# artik530_carrierboard.net
KiCad netlist of a schematic drawn in EAGLE
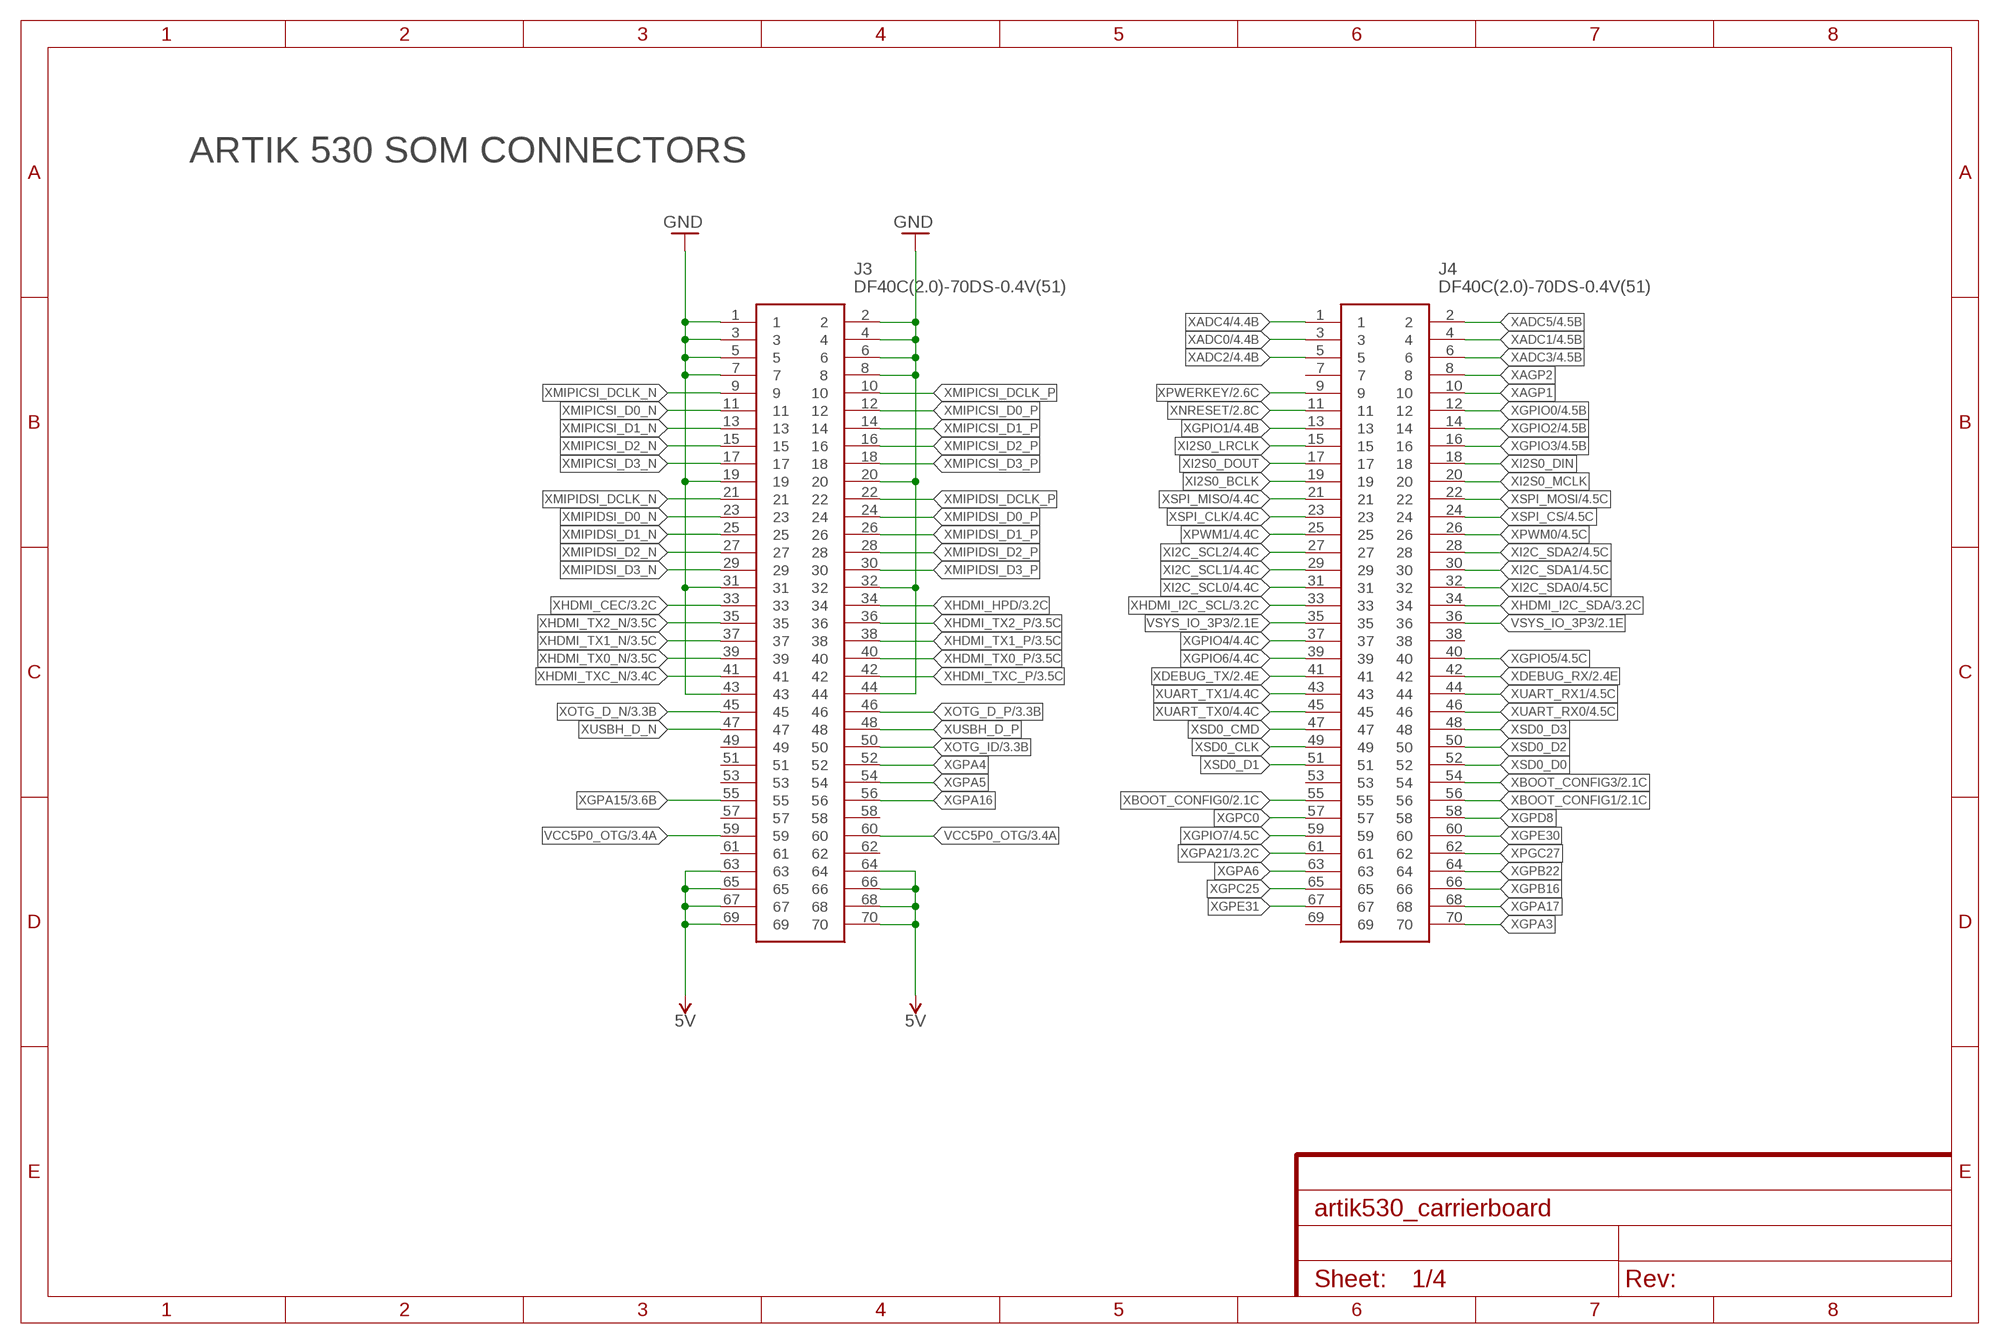
[diagram p0: schematic, sheet 1]
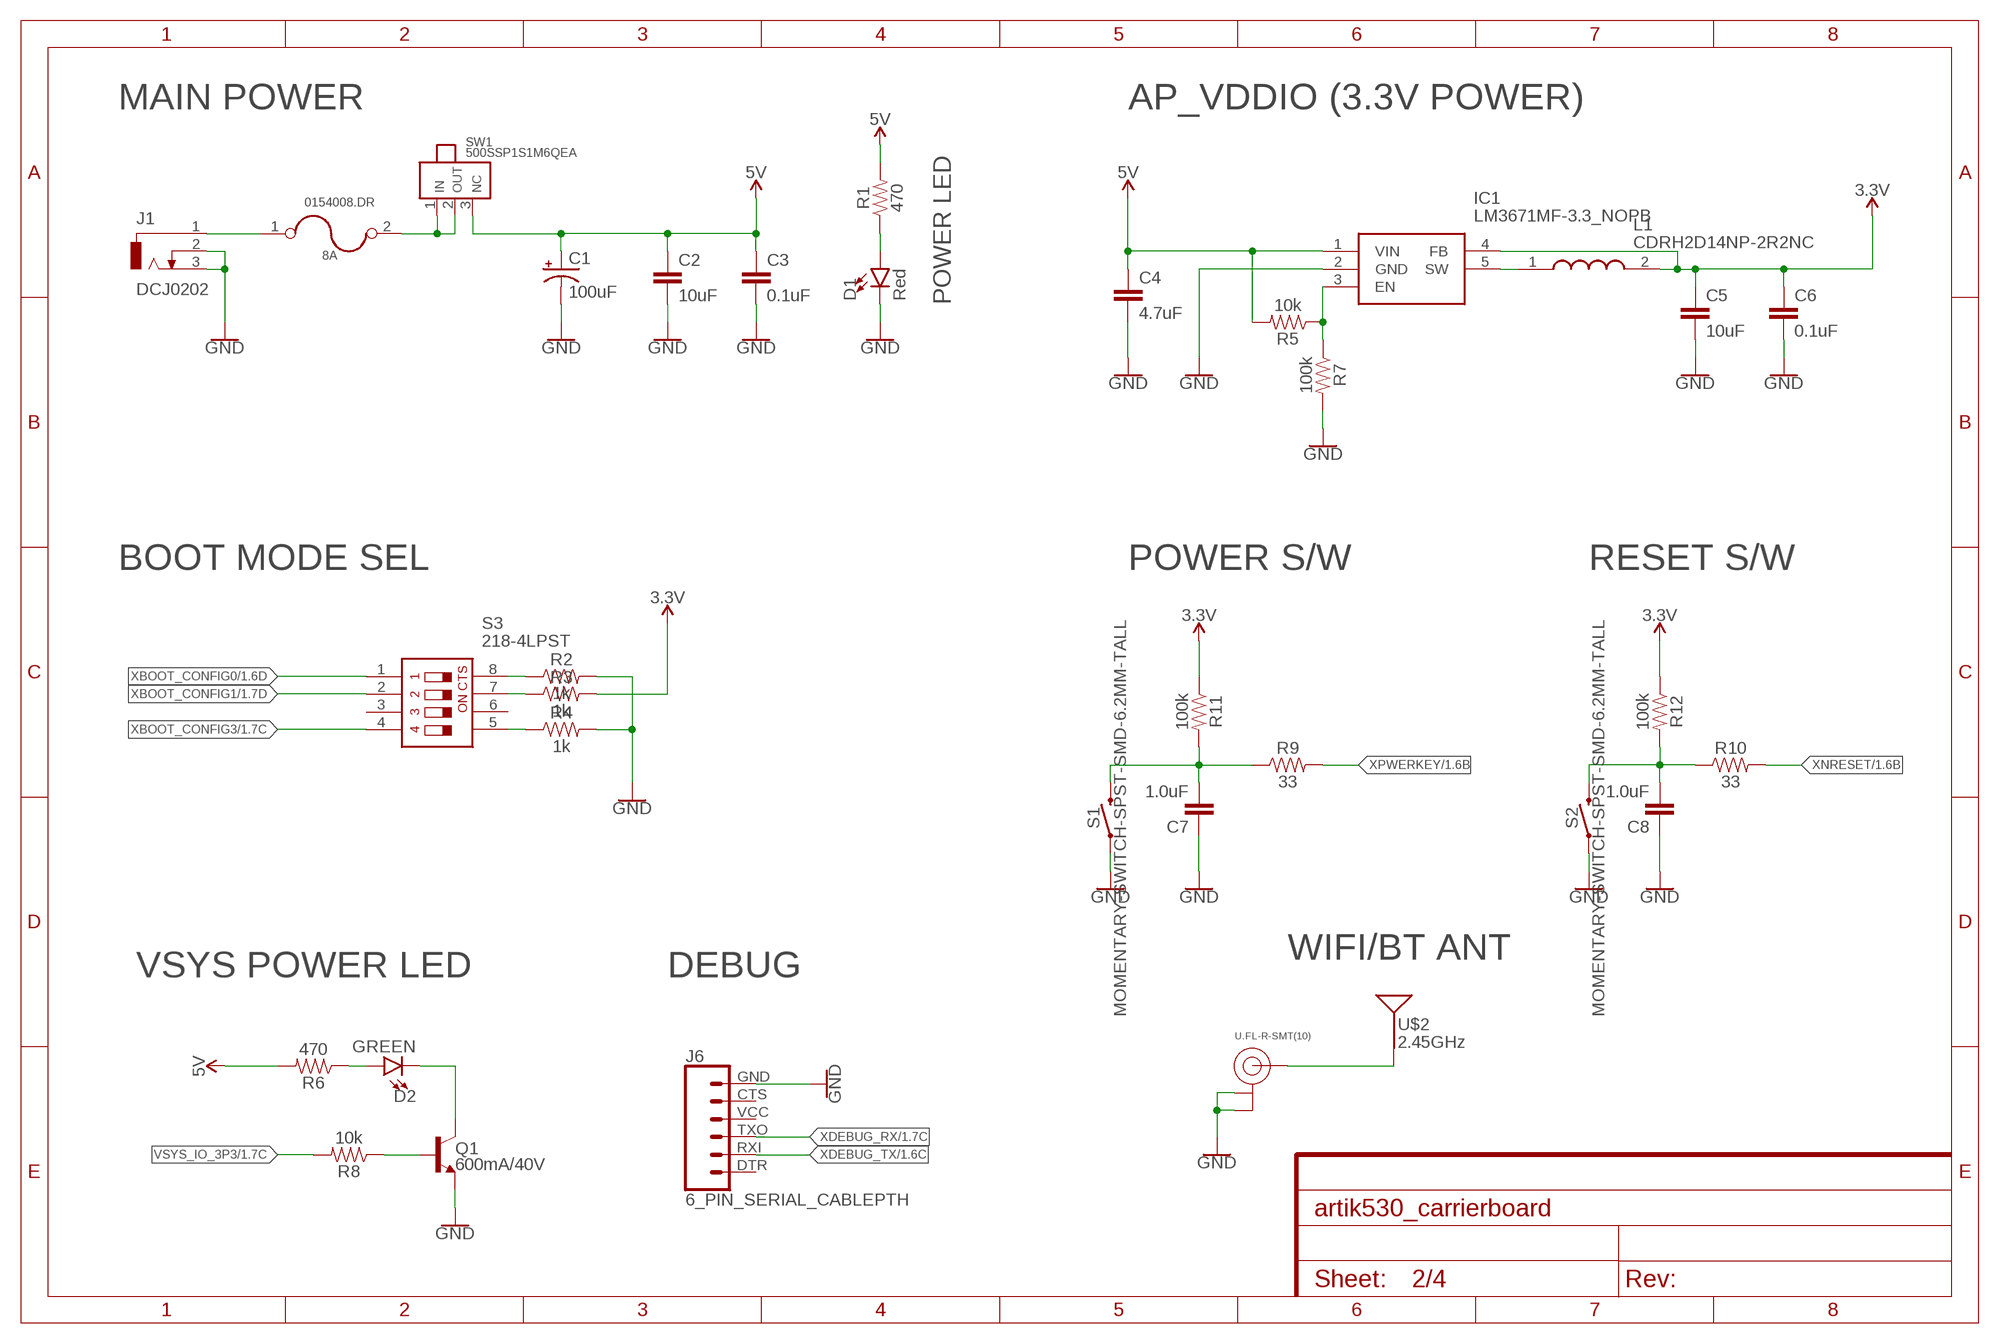
[diagram p1: schematic, sheet 2]
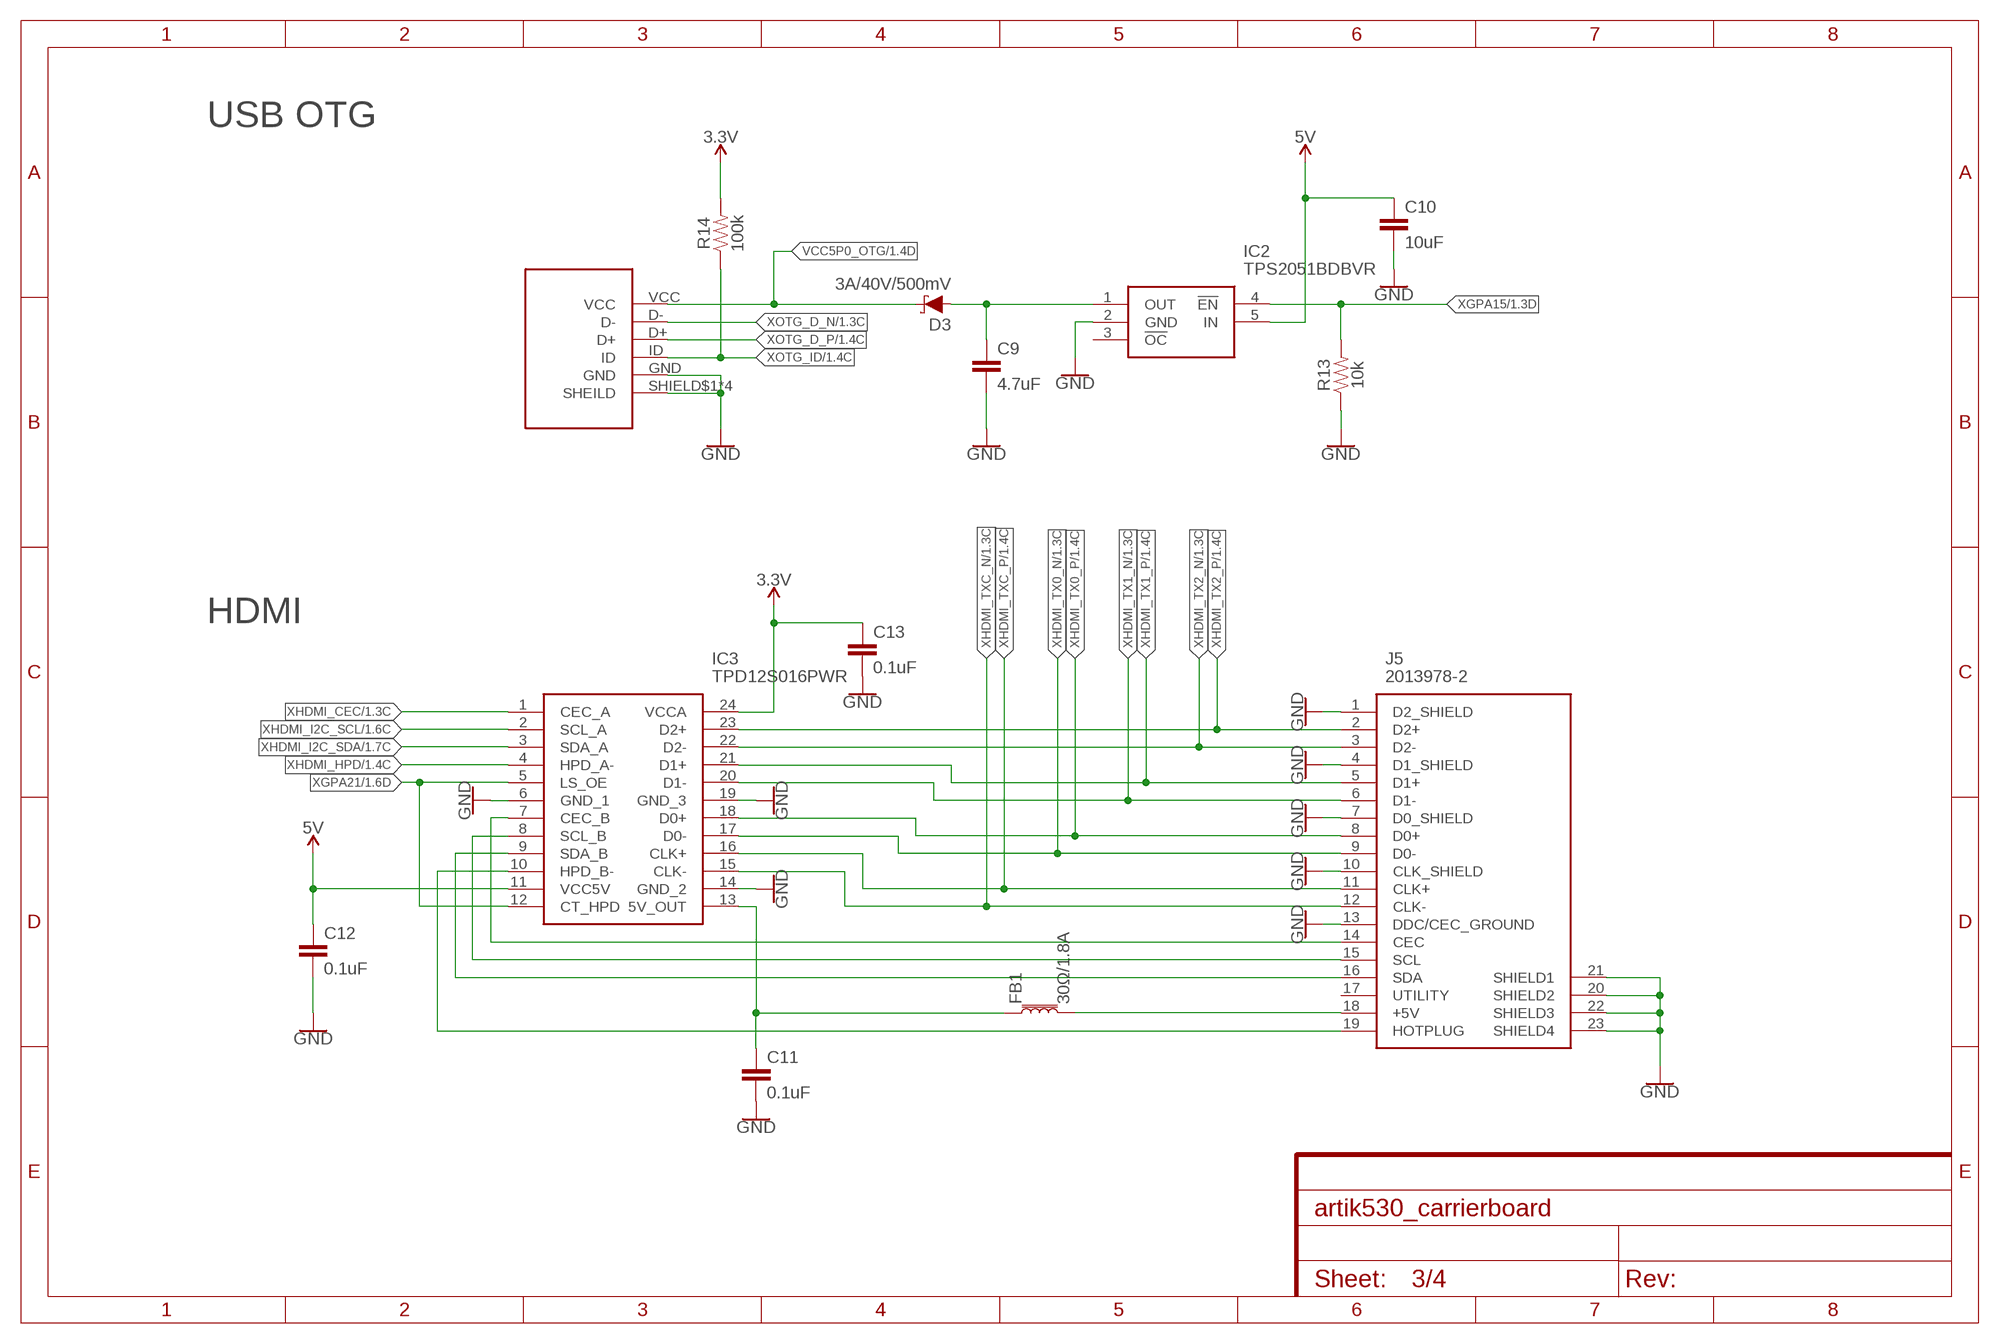
[diagram p2: schematic, sheet 3]
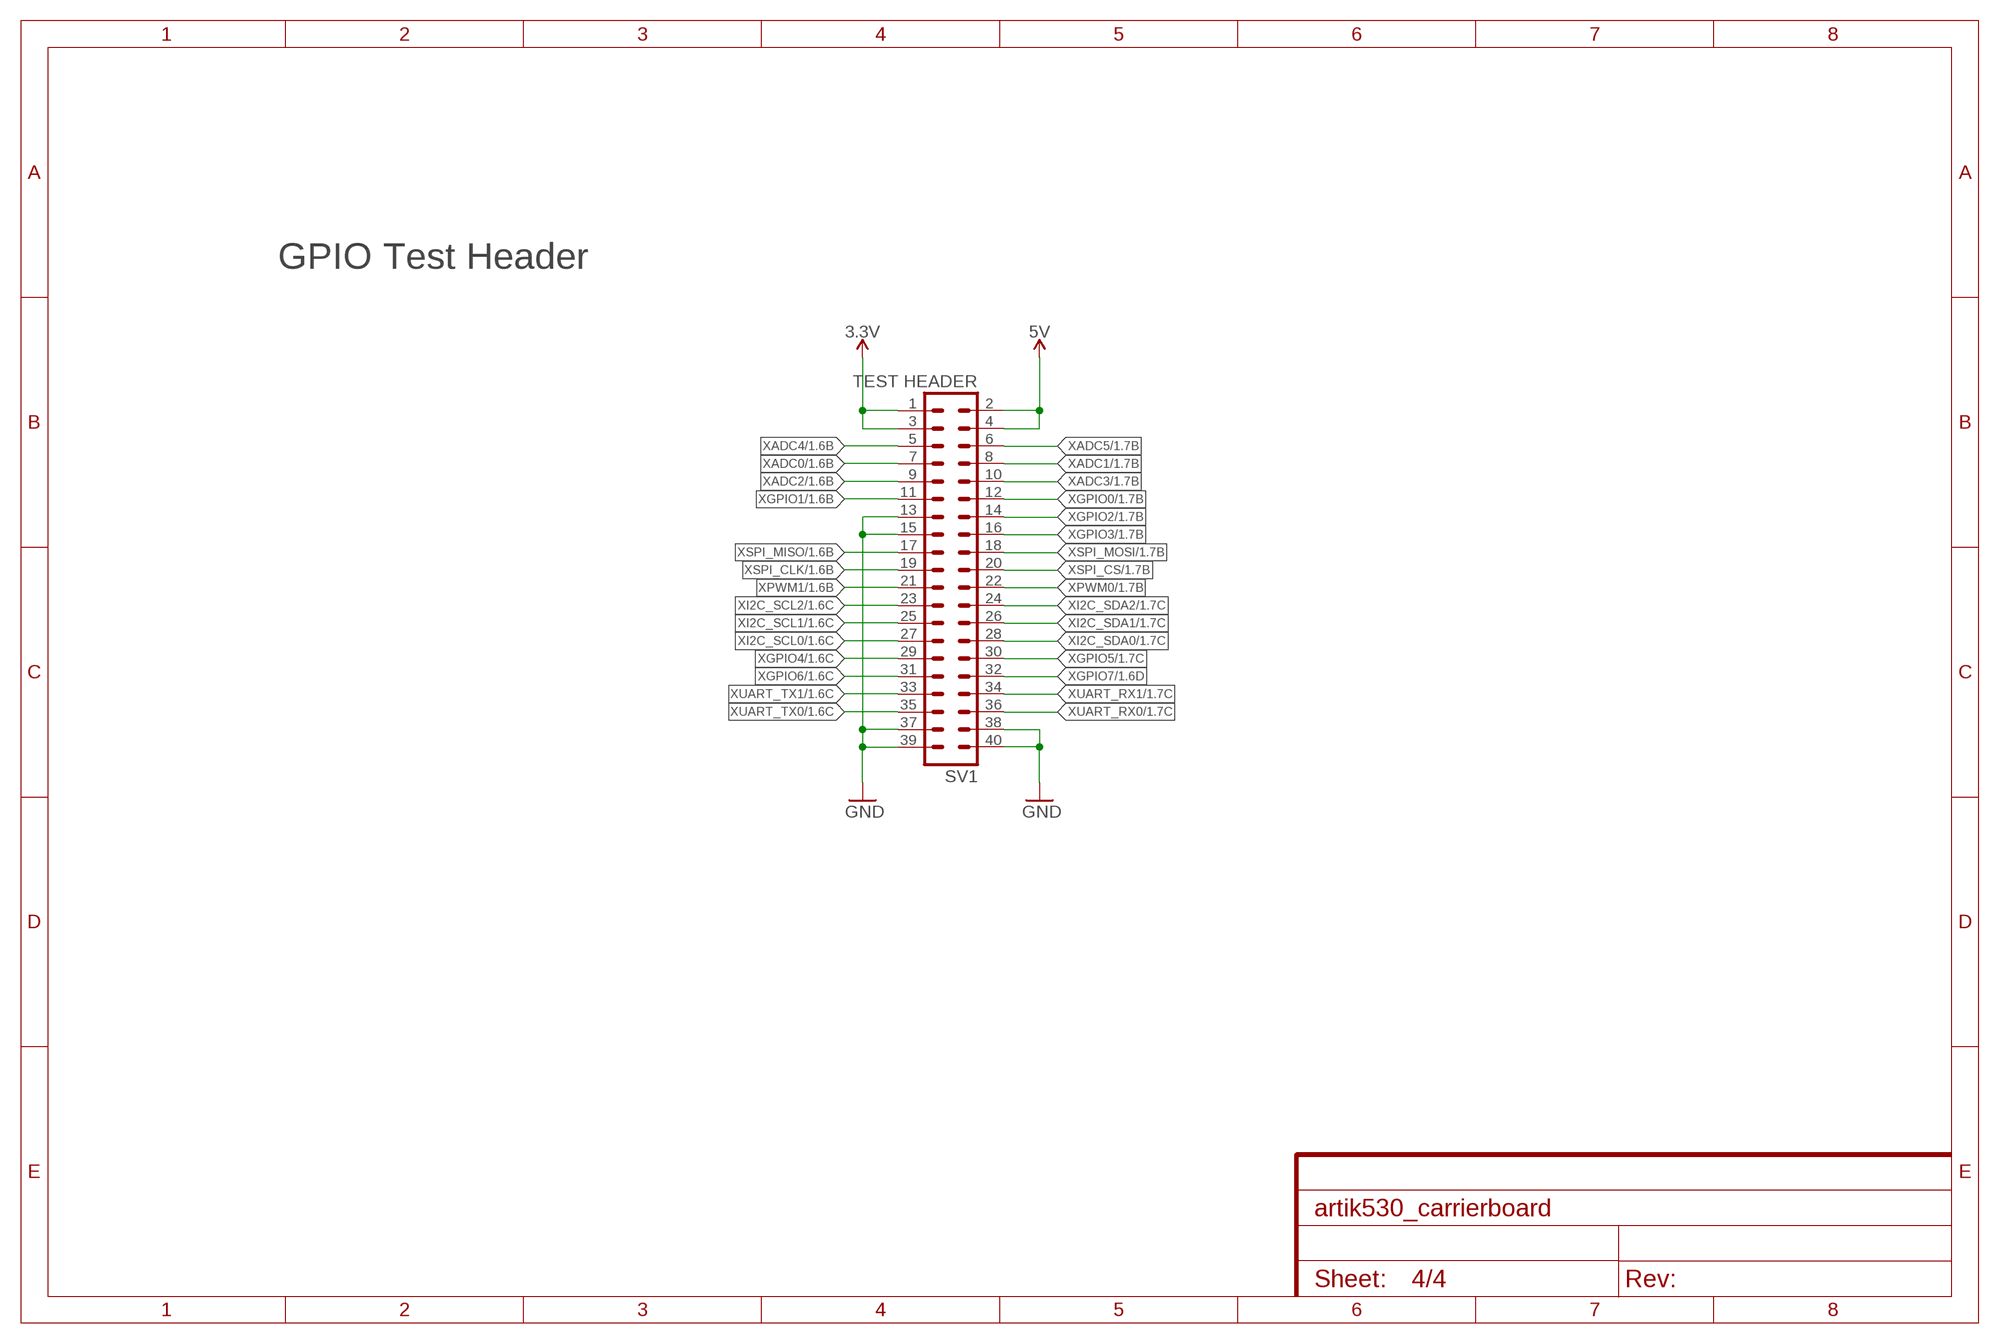
[diagram p3: schematic, sheet 4]

(export (version "E")
  (design (tool "Eeschema 10.0.6"))
  (components
    (comp (ref "J3")
      (value "DF40C(2.0)-70DS-0.4V(51)")
      (footprint "eagle-import:DF40C(2.0)-70DS-0.4V(51)")
      (libsource (lib "eagle-import") (part "DF40C(2.0)-70DS-0.4V(51)"))
    )
    (comp (ref "J4")
      (value "DF40C(2.0)-70DS-0.4V(51)")
      (footprint "eagle-import:DF40C(2.0)-70DS-0.4V(51)")
      (libsource (lib "eagle-import") (part "DF40C(2.0)-70DS-0.4V(51)"))
    )
    (comp (ref "SV1")
      (value "TEST HEADER")
      (footprint "eagle-import:MA20-2")
      (libsource (lib "eagle-import") (part "MA20-2"))
    )
    (comp (ref "C9")
      (value "4.7uF")
      (footprint "eagle-import:0603")
      (libsource (lib "eagle-import") (part "4.7UF-0603-6.3V-(10%)"))
    )
    (comp (ref "C10")
      (value "10uF")
      (footprint "eagle-import:0603")
      (libsource (lib "eagle-import") (part "10UF-0603-6.3V-20%"))
    )
    (comp (ref "C11")
      (value "0.1uF")
      (footprint "eagle-import:0603")
      (libsource (lib "eagle-import") (part "0.1UF-0603-25V-(+80/-20%)"))
    )
    (comp (ref "C12")
      (value "0.1uF")
      (footprint "eagle-import:0603")
      (libsource (lib "eagle-import") (part "0.1UF-0603-25V-(+80/-20%)"))
    )
    (comp (ref "C13")
      (value "0.1uF")
      (footprint "eagle-import:0603")
      (libsource (lib "eagle-import") (part "0.1UF-0603-25V-(+80/-20%)"))
    )
    (comp (ref "D3")
      (value "3A/40V/500mV")
      (footprint "eagle-import:SMA-DIODE")
      (libsource (lib "eagle-import") (part "DIODE-SCHOTTKY-B340A"))
    )
    (comp (ref "FB1")
      (value "30Ω/1.8A")
      (footprint "eagle-import:0603")
      (libsource (lib "eagle-import") (part "FERRITE_BEAD-0603"))
    )
    (comp (ref "IC2")
      (value "TPS2051BDBVR")
      (footprint "eagle-import:SOT95P280X145-5N")
      (libsource (lib "eagle-import") (part "TPS2051BDBVR"))
    )
    (comp (ref "IC3")
      (value "TPD12S016PWR")
      (footprint "eagle-import:SOP65P640X120-24N")
      (fields (field (name "RS_PART_NUMBER") "1627865"))
      (libsource (lib "eagle-import") (part "TPD12S016PWR"))
    )
    (comp (ref "J2")
      (value "10118193-0001LF")
      (footprint "eagle-import:10118193-0001LF")
      (libsource (lib "eagle-import") (part "10118193-0001LF"))
    )
    (comp (ref "J5")
      (value "2013978-2")
      (footprint "eagle-import:20139782")
      (libsource (lib "eagle-import") (part "2013978-2"))
    )
    (comp (ref "R13")
      (value "10k")
      (footprint "eagle-import:0603")
      (libsource (lib "eagle-import") (part "10KOHM-0603-1/10W-1%"))
    )
    (comp (ref "R14")
      (value "100k")
      (footprint "eagle-import:0603")
      (libsource (lib "eagle-import") (part "100KOHM-0603-1/10W-1%"))
    )
    (comp (ref "C1")
      (value "100uF")
      (footprint "eagle-import:EIA7343")
      (libsource (lib "eagle-import") (part "100UF-POLAR-EIA7343-10V-10%(TANT)"))
    )
    (comp (ref "C2")
      (value "10uF")
      (footprint "eagle-import:0603")
      (libsource (lib "eagle-import") (part "10UF-0603-6.3V-20%"))
    )
    (comp (ref "C3")
      (value "0.1uF")
      (footprint "eagle-import:0603")
      (libsource (lib "eagle-import") (part "0.1UF-0603-25V-(+80/-20%)"))
    )
    (comp (ref "C4")
      (value "4.7uF")
      (footprint "eagle-import:0603")
      (libsource (lib "eagle-import") (part "4.7UF-0603-6.3V-(10%)"))
    )
    (comp (ref "C5")
      (value "10uF")
      (footprint "eagle-import:0603")
      (libsource (lib "eagle-import") (part "10UF-0603-6.3V-20%"))
    )
    (comp (ref "C6")
      (value "0.1uF")
      (footprint "eagle-import:0603")
      (libsource (lib "eagle-import") (part "0.1UF-0603-25V-(+80/-20%)"))
    )
    (comp (ref "C7")
      (value "1.0uF")
      (footprint "eagle-import:0603")
      (libsource (lib "eagle-import") (part "1.0UF-0603-16V-10%"))
    )
    (comp (ref "C8")
      (value "1.0uF")
      (footprint "eagle-import:0603")
      (libsource (lib "eagle-import") (part "1.0UF-0603-16V-10%"))
    )
    (comp (ref "D1")
      (value "Red")
      (footprint "eagle-import:LED-0603")
      (libsource (lib "eagle-import") (part "LED-RED0603-SMART"))
    )
    (comp (ref "D2")
      (value "GREEN")
      (footprint "eagle-import:LED-0603")
      (libsource (lib "eagle-import") (part "LED-GREEN0603"))
    )
    (comp (ref "IC1")
      (value "LM3671MF-3.3_NOPB")
      (footprint "eagle-import:SOT95P284X122-5N")
      (fields
        (field (name "DIGIKEY_PART_NUMBER") "LM3671MF-3.3/NOPBTR-ND")
        (field (name "MANUFACTURER_PART_NUMBER") "LM3671MF-3.3/NOPB")
      )
      (libsource (lib "eagle-import") (part "LM3671MF-3.3_NOPB"))
    )
    (comp (ref "J1")
      (value "DCJ0202")
      (footprint "eagle-import:DCJ0202")
      (libsource (lib "eagle-import") (part "DCJ0202"))
    )
    (comp (ref "J6")
      (value "6_PIN_SERIAL_CABLEPTH")
      (footprint "eagle-import:FTDI_BASIC")
      (libsource (lib "eagle-import") (part "6_PIN_SERIAL_CABLEPTH"))
    )
    (comp (ref "L1")
      (value "CDRH2D14NP-2R2NC")
      (footprint "eagle-import:CDRH2D14")
      (libsource (lib "eagle-import") (part "CDRH2D14NP-2R2NC"))
    )
    (comp (ref "Q1")
      (value "600mA/40V")
      (footprint "eagle-import:SOT23-3")
      (libsource (lib "eagle-import") (part "TRANS_NPN-MMBT2222AL"))
    )
    (comp (ref "R1")
      (value "470")
      (footprint "eagle-import:0603")
      (libsource (lib "eagle-import") (part "470OHM-0603-1/10W-1%"))
    )
    (comp (ref "R2")
      (value "1k")
      (footprint "eagle-import:0603")
      (libsource (lib "eagle-import") (part "1KOHM-0603-1/10W-1%"))
    )
    (comp (ref "R3")
      (value "1k")
      (footprint "eagle-import:0603")
      (libsource (lib "eagle-import") (part "1KOHM-0603-1/10W-1%"))
    )
    (comp (ref "R4")
      (value "1k")
      (footprint "eagle-import:0603")
      (libsource (lib "eagle-import") (part "1KOHM-0603-1/10W-1%"))
    )
    (comp (ref "R5")
      (value "10k")
      (footprint "eagle-import:0603")
      (libsource (lib "eagle-import") (part "10KOHM-0603-1/10W-1%"))
    )
    (comp (ref "R6")
      (value "470")
      (footprint "eagle-import:0603")
      (libsource (lib "eagle-import") (part "470OHM-0603-1/10W-1%"))
    )
    (comp (ref "R7")
      (value "100k")
      (footprint "eagle-import:0603")
      (libsource (lib "eagle-import") (part "100KOHM-0603-1/10W-1%"))
    )
    (comp (ref "R8")
      (value "10k")
      (footprint "eagle-import:0603")
      (libsource (lib "eagle-import") (part "10KOHM-0603-1/10W-1%"))
    )
    (comp (ref "R9")
      (value "33")
      (footprint "eagle-import:0603")
      (libsource (lib "eagle-import") (part "33OHM-0603-1/10W-1%"))
    )
    (comp (ref "R10")
      (value "33")
      (footprint "eagle-import:0603")
      (libsource (lib "eagle-import") (part "33OHM-0603-1/10W-1%"))
    )
    (comp (ref "R11")
      (value "100k")
      (footprint "eagle-import:0603")
      (libsource (lib "eagle-import") (part "100KOHM-0603-1/10W-1%"))
    )
    (comp (ref "R12")
      (value "100k")
      (footprint "eagle-import:0603")
      (libsource (lib "eagle-import") (part "100KOHM-0603-1/10W-1%"))
    )
    (comp (ref "S1")
      (value "MOMENTARY-SWITCH-SPST-SMD-6.2MM-TALL")
      (footprint "eagle-import:TACTILE_SWITCH_SMD_6.2MM_TALL")
      (libsource (lib "eagle-import") (part "MOMENTARY-SWITCH-SPST-SMD-6.2MM-TALL"))
    )
    (comp (ref "S2")
      (value "MOMENTARY-SWITCH-SPST-SMD-6.2MM-TALL")
      (footprint "eagle-import:TACTILE_SWITCH_SMD_6.2MM_TALL")
      (libsource (lib "eagle-import") (part "MOMENTARY-SWITCH-SPST-SMD-6.2MM-TALL"))
    )
    (comp (ref "S3")
      (value "218-4LPST")
      (footprint "eagle-import:SOIC127P844X265-8N")
      (libsource (lib "eagle-import") (part "218-4LPST"))
    )
    (comp (ref "SW1")
      (value "500SSP1S1M6QEA")
      (footprint "eagle-import:500SSP1S1M6QEA")
      (libsource (lib "eagle-import") (part "500SSP1S1M6QEA"))
    )
    (comp (ref "U$1")
      (value "0154008.DR")
      (footprint "eagle-import:0154008.DR")
      (libsource (lib "eagle-import") (part "0154008.DR"))
    )
    (comp (ref "U$2")
      (value "2.45GHz")
      (footprint "eagle-import:ANT-2.4GHZ-6.5X2.2MM")
      (libsource (lib "eagle-import") (part "ANTENNA2.4GHZ-6.5X2.2MM"))
    )
    (comp (ref "U$3")
      (value "U.FL-R-SMT(10)")
      (footprint "eagle-import:U.FL-R-SMT(10)")
      (libsource (lib "eagle-import") (part "U.FL-R-SMT(10)"))
    )
  )
  (nets
    (net (code "1") (name "3.3V") (class "Default")
      (node (ref "C13") (pin "1") (pinfunction "1_1") (pintype "passive"))
      (node (ref "C5") (pin "1") (pinfunction "1_1") (pintype "passive"))
      (node (ref "C6") (pin "1") (pinfunction "1_1") (pintype "passive"))
      (node (ref "IC1") (pin "4") (pinfunction "FB_4") (pintype "bidirectional"))
      (node (ref "IC3") (pin "24") (pinfunction "VCCA_24") (pintype "bidirectional"))
      (node (ref "L1") (pin "2") (pinfunction "2_2") (pintype "bidirectional"))
      (node (ref "R11") (pin "1") (pinfunction "1_1") (pintype "passive"))
      (node (ref "R12") (pin "1") (pinfunction "1_1") (pintype "passive"))
      (node (ref "R14") (pin "2") (pinfunction "2_2") (pintype "passive"))
      (node (ref "R3") (pin "2") (pinfunction "2_2") (pintype "passive"))
      (node (ref "SV1") (pin "1") (pinfunction "1_1") (pintype "passive"))
      (node (ref "SV1") (pin "3") (pinfunction "3_3") (pintype "passive"))
    )
    (net (code "2") (name "5V") (class "Default")
      (node (ref "C1") (pin "A") (pinfunction "+_A") (pintype "passive"))
      (node (ref "C10") (pin "1") (pinfunction "1_1") (pintype "passive"))
      (node (ref "C12") (pin "1") (pinfunction "1_1") (pintype "passive"))
      (node (ref "C2") (pin "1") (pinfunction "1_1") (pintype "passive"))
      (node (ref "C3") (pin "1") (pinfunction "1_1") (pintype "passive"))
      (node (ref "C4") (pin "1") (pinfunction "1_1") (pintype "passive"))
      (node (ref "IC1") (pin "1") (pinfunction "VIN_1") (pintype "bidirectional"))
      (node (ref "IC2") (pin "5") (pinfunction "IN_5") (pintype "input"))
      (node (ref "IC3") (pin "11") (pinfunction "VCC5V_11") (pintype "bidirectional"))
      (node (ref "J3") (pin "63") (pinfunction "63_63") (pintype "bidirectional"))
      (node (ref "J3") (pin "64") (pinfunction "64_64") (pintype "bidirectional"))
      (node (ref "J3") (pin "65") (pinfunction "65_65") (pintype "bidirectional"))
      (node (ref "J3") (pin "66") (pinfunction "66_66") (pintype "bidirectional"))
      (node (ref "J3") (pin "67") (pinfunction "67_67") (pintype "bidirectional"))
      (node (ref "J3") (pin "68") (pinfunction "68_68") (pintype "bidirectional"))
      (node (ref "J3") (pin "69") (pinfunction "69_69") (pintype "bidirectional"))
      (node (ref "J3") (pin "70") (pinfunction "70_70") (pintype "bidirectional"))
      (node (ref "R1") (pin "2") (pinfunction "2_2") (pintype "passive"))
      (node (ref "R5") (pin "2") (pinfunction "2_2") (pintype "passive"))
      (node (ref "R6") (pin "2") (pinfunction "2_2") (pintype "passive"))
      (node (ref "SV1") (pin "2") (pinfunction "2_2") (pintype "passive"))
      (node (ref "SV1") (pin "4") (pinfunction "4_4") (pintype "passive"))
      (node (ref "SW1") (pin "3") (pinfunction "NC_3") (pintype "bidirectional"))
    )
    (net (code "3") (name "GND") (class "Default")
      (node (ref "C1") (pin "C") (pinfunction "-_C") (pintype "passive"))
      (node (ref "C10") (pin "2") (pinfunction "2_2") (pintype "passive"))
      (node (ref "C11") (pin "2") (pinfunction "2_2") (pintype "passive"))
      (node (ref "C12") (pin "2") (pinfunction "2_2") (pintype "passive"))
      (node (ref "C13") (pin "2") (pinfunction "2_2") (pintype "passive"))
      (node (ref "C2") (pin "2") (pinfunction "2_2") (pintype "passive"))
      (node (ref "C3") (pin "2") (pinfunction "2_2") (pintype "passive"))
      (node (ref "C4") (pin "2") (pinfunction "2_2") (pintype "passive"))
      (node (ref "C5") (pin "2") (pinfunction "2_2") (pintype "passive"))
      (node (ref "C6") (pin "2") (pinfunction "2_2") (pintype "passive"))
      (node (ref "C7") (pin "1") (pinfunction "1_1") (pintype "passive"))
      (node (ref "C8") (pin "1") (pinfunction "1_1") (pintype "passive"))
      (node (ref "C9") (pin "2") (pinfunction "2_2") (pintype "passive"))
      (node (ref "D1") (pin "C") (pinfunction "C_C") (pintype "passive"))
      (node (ref "IC1") (pin "2") (pinfunction "GND_2") (pintype "bidirectional"))
      (node (ref "IC2") (pin "2") (pinfunction "GND_2") (pintype "power_in"))
      (node (ref "IC3") (pin "14") (pinfunction "GND_2_14") (pintype "bidirectional"))
      (node (ref "IC3") (pin "19") (pinfunction "GND_3_19") (pintype "bidirectional"))
      (node (ref "IC3") (pin "6") (pinfunction "GND_1_6") (pintype "bidirectional"))
      (node (ref "J1") (pin "2") (pinfunction "2_2") (pintype "passive"))
      (node (ref "J1") (pin "3") (pinfunction "3_3") (pintype "passive"))
      (node (ref "J2") (pin "GND") (pinfunction "GND_GND") (pintype "bidirectional"))
      (node (ref "J2") (pin "SHIELD$1") (pinfunction "SHEILD_SHIELD$1") (pintype "bidirectional"))
      (node (ref "J2") (pin "SHIELD$2") (pinfunction "SHEILD_SHIELD$2") (pintype "bidirectional"))
      (node (ref "J2") (pin "SHIELD$3") (pinfunction "SHEILD_SHIELD$3") (pintype "bidirectional"))
      (node (ref "J2") (pin "SHIELD$4") (pinfunction "SHEILD_SHIELD$4") (pintype "bidirectional"))
      (node (ref "J3") (pin "1") (pinfunction "1_1") (pintype "bidirectional"))
      (node (ref "J3") (pin "19") (pinfunction "19_19") (pintype "bidirectional"))
      (node (ref "J3") (pin "2") (pinfunction "2_2") (pintype "bidirectional"))
      (node (ref "J3") (pin "20") (pinfunction "20_20") (pintype "bidirectional"))
      (node (ref "J3") (pin "3") (pinfunction "3_3") (pintype "bidirectional"))
      (node (ref "J3") (pin "31") (pinfunction "31_31") (pintype "bidirectional"))
      (node (ref "J3") (pin "32") (pinfunction "32_32") (pintype "bidirectional"))
      (node (ref "J3") (pin "4") (pinfunction "4_4") (pintype "bidirectional"))
      (node (ref "J3") (pin "43") (pinfunction "43_43") (pintype "bidirectional"))
      (node (ref "J3") (pin "44") (pinfunction "44_44") (pintype "bidirectional"))
      (node (ref "J3") (pin "5") (pinfunction "5_5") (pintype "bidirectional"))
      (node (ref "J3") (pin "6") (pinfunction "6_6") (pintype "bidirectional"))
      (node (ref "J3") (pin "7") (pinfunction "7_7") (pintype "bidirectional"))
      (node (ref "J3") (pin "8") (pinfunction "8_8") (pintype "bidirectional"))
      (node (ref "J5") (pin "1") (pinfunction "D2_SHIELD_1") (pintype "bidirectional"))
      (node (ref "J5") (pin "10") (pinfunction "CLK_SHIELD_10") (pintype "bidirectional"))
      (node (ref "J5") (pin "13") (pinfunction "DDC/CEC_GROUND_13") (pintype "bidirectional"))
      (node (ref "J5") (pin "20") (pinfunction "SHIELD2_20") (pintype "bidirectional"))
      (node (ref "J5") (pin "21") (pinfunction "SHIELD1_21") (pintype "bidirectional"))
      (node (ref "J5") (pin "22") (pinfunction "SHIELD3_22") (pintype "bidirectional"))
      (node (ref "J5") (pin "23") (pinfunction "SHIELD4_23") (pintype "bidirectional"))
      (node (ref "J5") (pin "4") (pinfunction "D1_SHIELD_4") (pintype "bidirectional"))
      (node (ref "J5") (pin "7") (pinfunction "D0_SHIELD_7") (pintype "bidirectional"))
      (node (ref "J6") (pin "GND") (pinfunction "6_GND") (pintype "passive"))
      (node (ref "Q1") (pin "2") (pinfunction "E_2") (pintype "passive"))
      (node (ref "R13") (pin "1") (pinfunction "1_1") (pintype "passive"))
      (node (ref "R2") (pin "2") (pinfunction "2_2") (pintype "passive"))
      (node (ref "R4") (pin "2") (pinfunction "2_2") (pintype "passive"))
      (node (ref "R7") (pin "2") (pinfunction "2_2") (pintype "passive"))
      (node (ref "S1") (pin "A2") (pinfunction "1_A2") (pintype "passive"))
      (node (ref "S2") (pin "A2") (pinfunction "1_A2") (pintype "passive"))
      (node (ref "SV1") (pin "13") (pinfunction "13_13") (pintype "passive"))
      (node (ref "SV1") (pin "15") (pinfunction "15_15") (pintype "passive"))
      (node (ref "SV1") (pin "37") (pinfunction "37_37") (pintype "passive"))
      (node (ref "SV1") (pin "38") (pinfunction "38_38") (pintype "passive"))
      (node (ref "SV1") (pin "39") (pinfunction "39_39") (pintype "passive"))
      (node (ref "SV1") (pin "40") (pinfunction "40_40") (pintype "passive"))
      (node (ref "U$3") (pin "1") (pinfunction "GND1_1") (pintype "bidirectional"))
      (node (ref "U$3") (pin "2") (pinfunction "GND2_2") (pintype "bidirectional"))
    )
    (net (code "4") (name "Net-(D1-PadA)") (class "Default")
      (node (ref "D1") (pin "A") (pinfunction "A_A") (pintype "passive"))
      (node (ref "R1") (pin "1") (pinfunction "1_1") (pintype "passive"))
    )
    (net (code "5") (name "Net-(D2-PadA)") (class "Default")
      (node (ref "D2") (pin "A") (pinfunction "A_A") (pintype "passive"))
      (node (ref "R6") (pin "1") (pinfunction "1_1") (pintype "passive"))
    )
    (net (code "6") (name "Net-(IC1-EN)") (class "Default")
      (node (ref "IC1") (pin "3") (pinfunction "EN_3") (pintype "bidirectional"))
      (node (ref "R5") (pin "1") (pinfunction "1_1") (pintype "passive"))
      (node (ref "R7") (pin "1") (pinfunction "1_1") (pintype "passive"))
    )
    (net (code "7") (name "Net-(IC1-SW)") (class "Default")
      (node (ref "IC1") (pin "5") (pinfunction "SW_5") (pintype "bidirectional"))
      (node (ref "L1") (pin "1") (pinfunction "1_1") (pintype "bidirectional"))
    )
    (net (code "8") (name "Net-(IC2-OUT)") (class "Default")
      (node (ref "C9") (pin "1") (pinfunction "1_1") (pintype "passive"))
      (node (ref "D3") (pin "A") (pinfunction "A_A") (pintype "passive"))
      (node (ref "IC2") (pin "1") (pinfunction "OUT_1") (pintype "output"))
    )
    (net (code "9") (name "Net-(IC3-5V_OUT)") (class "Default")
      (node (ref "C11") (pin "1") (pinfunction "1_1") (pintype "passive"))
      (node (ref "FB1") (pin "1") (pinfunction "1_1") (pintype "passive"))
      (node (ref "IC3") (pin "13") (pinfunction "5V_OUT_13") (pintype "output"))
    )
    (net (code "10") (name "Net-(IC3-CEC_B)") (class "Default")
      (node (ref "IC3") (pin "7") (pinfunction "CEC_B_7") (pintype "bidirectional"))
      (node (ref "J5") (pin "14") (pinfunction "CEC_14") (pintype "bidirectional"))
    )
    (net (code "11") (name "Net-(IC3-HPD_B-)") (class "Default")
      (node (ref "IC3") (pin "10") (pinfunction "HPD_B-_10") (pintype "bidirectional"))
      (node (ref "J5") (pin "19") (pinfunction "HOTPLUG_19") (pintype "bidirectional"))
    )
    (net (code "12") (name "Net-(IC3-SCL_B)") (class "Default")
      (node (ref "IC3") (pin "8") (pinfunction "SCL_B_8") (pintype "bidirectional"))
      (node (ref "J5") (pin "15") (pinfunction "SCL_15") (pintype "bidirectional"))
    )
    (net (code "13") (name "Net-(IC3-SDA_B)") (class "Default")
      (node (ref "IC3") (pin "9") (pinfunction "SDA_B_9") (pintype "bidirectional"))
      (node (ref "J5") (pin "16") (pinfunction "SDA_16") (pintype "bidirectional"))
    )
    (net (code "14") (name "Net-(J1-Pad1)") (class "Default")
      (node (ref "J1") (pin "1") (pinfunction "1_1") (pintype "passive"))
      (node (ref "U$1") (pin "1") (pinfunction "1_1") (pintype "bidirectional"))
    )
    (net (code "15") (name "Net-(J5-+5V)") (class "Default")
      (node (ref "FB1") (pin "2") (pinfunction "2_2") (pintype "passive"))
      (node (ref "J5") (pin "18") (pinfunction "+5V_18") (pintype "bidirectional"))
    )
    (net (code "16") (name "Net-(Q1-B)") (class "Default")
      (node (ref "Q1") (pin "1") (pinfunction "B_1") (pintype "passive"))
      (node (ref "R8") (pin "1") (pinfunction "1_1") (pintype "passive"))
    )
    (net (code "17") (name "Net-(Q1-C)") (class "Default")
      (node (ref "D2") (pin "C") (pinfunction "C_C") (pintype "passive"))
      (node (ref "Q1") (pin "3") (pinfunction "C_3") (pintype "passive"))
    )
    (net (code "18") (name "Net-(R2-Pad1)") (class "Default")
      (node (ref "R2") (pin "1") (pinfunction "1_1") (pintype "passive"))
      (node (ref "S3") (pin "8") (pinfunction "8_8") (pintype "bidirectional"))
    )
    (net (code "19") (name "Net-(R3-Pad1)") (class "Default")
      (node (ref "R3") (pin "1") (pinfunction "1_1") (pintype "passive"))
      (node (ref "S3") (pin "7") (pinfunction "7_7") (pintype "bidirectional"))
    )
    (net (code "20") (name "Net-(R4-Pad1)") (class "Default")
      (node (ref "R4") (pin "1") (pinfunction "1_1") (pintype "passive"))
      (node (ref "S3") (pin "5") (pinfunction "5_5") (pintype "bidirectional"))
    )
    (net (code "21") (name "Net-(S1-2)") (class "Default")
      (node (ref "C7") (pin "2") (pinfunction "2_2") (pintype "passive"))
      (node (ref "R11") (pin "2") (pinfunction "2_2") (pintype "passive"))
      (node (ref "R9") (pin "1") (pinfunction "1_1") (pintype "passive"))
      (node (ref "S1") (pin "B2") (pinfunction "2_B2") (pintype "passive"))
    )
    (net (code "22") (name "Net-(S2-2)") (class "Default")
      (node (ref "C8") (pin "2") (pinfunction "2_2") (pintype "passive"))
      (node (ref "R10") (pin "1") (pinfunction "1_1") (pintype "passive"))
      (node (ref "R12") (pin "2") (pinfunction "2_2") (pintype "passive"))
      (node (ref "S2") (pin "B2") (pinfunction "2_B2") (pintype "passive"))
    )
    (net (code "23") (name "Net-(SW1-IN)") (class "Default")
      (node (ref "SW1") (pin "1") (pinfunction "IN_1") (pintype "bidirectional"))
      (node (ref "SW1") (pin "2") (pinfunction "OUT_2") (pintype "bidirectional"))
      (node (ref "U$1") (pin "2") (pinfunction "2_2") (pintype "bidirectional"))
    )
    (net (code "24") (name "Net-(U$2-SIGNAL)") (class "Default")
      (node (ref "U$2") (pin "FEED") (pinfunction "SIGNAL_FEED") (pintype "bidirectional"))
      (node (ref "U$3") (pin "3") (pinfunction "SIG_3") (pintype "bidirectional"))
    )
    (net (code "25") (name "VCC5P0_OTG") (class "Default")
      (node (ref "D3") (pin "C") (pinfunction "C_C") (pintype "passive"))
      (node (ref "J2") (pin "VCC") (pinfunction "VCC_VCC") (pintype "bidirectional"))
      (node (ref "J3") (pin "59") (pinfunction "59_59") (pintype "bidirectional"))
      (node (ref "J3") (pin "60") (pinfunction "60_60") (pintype "bidirectional"))
    )
    (net (code "26") (name "VSYS_IO_3P3") (class "Default")
      (node (ref "J4") (pin "35") (pinfunction "35_35") (pintype "bidirectional"))
      (node (ref "J4") (pin "36") (pinfunction "36_36") (pintype "bidirectional"))
      (node (ref "R8") (pin "2") (pinfunction "2_2") (pintype "passive"))
    )
    (net (code "27") (name "XADC0") (class "Default")
      (node (ref "J4") (pin "3") (pinfunction "3_3") (pintype "bidirectional"))
      (node (ref "SV1") (pin "7") (pinfunction "7_7") (pintype "passive"))
    )
    (net (code "28") (name "XADC1") (class "Default")
      (node (ref "J4") (pin "4") (pinfunction "4_4") (pintype "bidirectional"))
      (node (ref "SV1") (pin "8") (pinfunction "8_8") (pintype "passive"))
    )
    (net (code "29") (name "XADC2") (class "Default")
      (node (ref "J4") (pin "5") (pinfunction "5_5") (pintype "bidirectional"))
      (node (ref "SV1") (pin "9") (pinfunction "9_9") (pintype "passive"))
    )
    (net (code "30") (name "XADC3") (class "Default")
      (node (ref "J4") (pin "6") (pinfunction "6_6") (pintype "bidirectional"))
      (node (ref "SV1") (pin "10") (pinfunction "10_10") (pintype "passive"))
    )
    (net (code "31") (name "XADC4") (class "Default")
      (node (ref "J4") (pin "1") (pinfunction "1_1") (pintype "bidirectional"))
      (node (ref "SV1") (pin "5") (pinfunction "5_5") (pintype "passive"))
    )
    (net (code "32") (name "XADC5") (class "Default")
      (node (ref "J4") (pin "2") (pinfunction "2_2") (pintype "bidirectional"))
      (node (ref "SV1") (pin "6") (pinfunction "6_6") (pintype "passive"))
    )
    (net (code "33") (name "XAGP1") (class "Default")
      (node (ref "J4") (pin "10") (pinfunction "10_10") (pintype "bidirectional"))
    )
    (net (code "34") (name "XAGP2") (class "Default")
      (node (ref "J4") (pin "8") (pinfunction "8_8") (pintype "bidirectional"))
    )
    (net (code "35") (name "XBOOT_CONFIG0") (class "Default")
      (node (ref "J4") (pin "55") (pinfunction "55_55") (pintype "bidirectional"))
      (node (ref "S3") (pin "1") (pinfunction "1_1") (pintype "bidirectional"))
    )
    (net (code "36") (name "XBOOT_CONFIG1") (class "Default")
      (node (ref "J4") (pin "56") (pinfunction "56_56") (pintype "bidirectional"))
      (node (ref "S3") (pin "2") (pinfunction "2_2") (pintype "bidirectional"))
    )
    (net (code "37") (name "XBOOT_CONFIG3") (class "Default")
      (node (ref "J4") (pin "54") (pinfunction "54_54") (pintype "bidirectional"))
      (node (ref "S3") (pin "4") (pinfunction "4_4") (pintype "bidirectional"))
    )
    (net (code "38") (name "XDEBUG_RX") (class "Default")
      (node (ref "J4") (pin "42") (pinfunction "42_42") (pintype "bidirectional"))
      (node (ref "J6") (pin "TXO") (pinfunction "3_TXO") (pintype "passive"))
    )
    (net (code "39") (name "XDEBUG_TX") (class "Default")
      (node (ref "J4") (pin "41") (pinfunction "41_41") (pintype "bidirectional"))
      (node (ref "J6") (pin "RXI") (pinfunction "2_RXI") (pintype "passive"))
    )
    (net (code "40") (name "XGPA3") (class "Default")
      (node (ref "J4") (pin "70") (pinfunction "70_70") (pintype "bidirectional"))
    )
    (net (code "41") (name "XGPA4") (class "Default")
      (node (ref "J3") (pin "52") (pinfunction "52_52") (pintype "bidirectional"))
    )
    (net (code "42") (name "XGPA5") (class "Default")
      (node (ref "J3") (pin "54") (pinfunction "54_54") (pintype "bidirectional"))
    )
    (net (code "43") (name "XGPA6") (class "Default")
      (node (ref "J4") (pin "63") (pinfunction "63_63") (pintype "bidirectional"))
    )
    (net (code "44") (name "XGPA15") (class "Default")
      (node (ref "IC2") (pin "4") (pinfunction "~{EN}_4") (pintype "bidirectional"))
      (node (ref "J3") (pin "55") (pinfunction "55_55") (pintype "bidirectional"))
      (node (ref "R13") (pin "2") (pinfunction "2_2") (pintype "passive"))
    )
    (net (code "45") (name "XGPA16") (class "Default")
      (node (ref "J3") (pin "56") (pinfunction "56_56") (pintype "bidirectional"))
    )
    (net (code "46") (name "XGPA17") (class "Default")
      (node (ref "J4") (pin "68") (pinfunction "68_68") (pintype "bidirectional"))
    )
    (net (code "47") (name "XGPA21") (class "Default")
      (node (ref "IC3") (pin "12") (pinfunction "CT_HPD_12") (pintype "bidirectional"))
      (node (ref "IC3") (pin "5") (pinfunction "LS_OE_5") (pintype "bidirectional"))
      (node (ref "J4") (pin "61") (pinfunction "61_61") (pintype "bidirectional"))
    )
    (net (code "48") (name "XGPB16") (class "Default")
      (node (ref "J4") (pin "66") (pinfunction "66_66") (pintype "bidirectional"))
    )
    (net (code "49") (name "XGPB22") (class "Default")
      (node (ref "J4") (pin "64") (pinfunction "64_64") (pintype "bidirectional"))
    )
    (net (code "50") (name "XGPC0") (class "Default")
      (node (ref "J4") (pin "57") (pinfunction "57_57") (pintype "bidirectional"))
    )
    (net (code "51") (name "XGPC25") (class "Default")
      (node (ref "J4") (pin "65") (pinfunction "65_65") (pintype "bidirectional"))
    )
    (net (code "52") (name "XGPD8") (class "Default")
      (node (ref "J4") (pin "58") (pinfunction "58_58") (pintype "bidirectional"))
    )
    (net (code "53") (name "XGPE30") (class "Default")
      (node (ref "J4") (pin "60") (pinfunction "60_60") (pintype "bidirectional"))
    )
    (net (code "54") (name "XGPE31") (class "Default")
      (node (ref "J4") (pin "67") (pinfunction "67_67") (pintype "bidirectional"))
    )
    (net (code "55") (name "XGPIO0") (class "Default")
      (node (ref "J4") (pin "12") (pinfunction "12_12") (pintype "bidirectional"))
      (node (ref "SV1") (pin "12") (pinfunction "12_12") (pintype "passive"))
    )
    (net (code "56") (name "XGPIO1") (class "Default")
      (node (ref "J4") (pin "13") (pinfunction "13_13") (pintype "bidirectional"))
      (node (ref "SV1") (pin "11") (pinfunction "11_11") (pintype "passive"))
    )
    (net (code "57") (name "XGPIO2") (class "Default")
      (node (ref "J4") (pin "14") (pinfunction "14_14") (pintype "bidirectional"))
      (node (ref "SV1") (pin "14") (pinfunction "14_14") (pintype "passive"))
    )
    (net (code "58") (name "XGPIO3") (class "Default")
      (node (ref "J4") (pin "16") (pinfunction "16_16") (pintype "bidirectional"))
      (node (ref "SV1") (pin "16") (pinfunction "16_16") (pintype "passive"))
    )
    (net (code "59") (name "XGPIO4") (class "Default")
      (node (ref "J4") (pin "37") (pinfunction "37_37") (pintype "bidirectional"))
      (node (ref "SV1") (pin "29") (pinfunction "29_29") (pintype "passive"))
    )
    (net (code "60") (name "XGPIO5") (class "Default")
      (node (ref "J4") (pin "40") (pinfunction "40_40") (pintype "bidirectional"))
      (node (ref "SV1") (pin "30") (pinfunction "30_30") (pintype "passive"))
    )
    (net (code "61") (name "XGPIO6") (class "Default")
      (node (ref "J4") (pin "39") (pinfunction "39_39") (pintype "bidirectional"))
      (node (ref "SV1") (pin "31") (pinfunction "31_31") (pintype "passive"))
    )
    (net (code "62") (name "XGPIO7") (class "Default")
      (node (ref "J4") (pin "59") (pinfunction "59_59") (pintype "bidirectional"))
      (node (ref "SV1") (pin "32") (pinfunction "32_32") (pintype "passive"))
    )
    (net (code "63") (name "XHDMI_CEC") (class "Default")
      (node (ref "IC3") (pin "1") (pinfunction "CEC_A_1") (pintype "bidirectional"))
      (node (ref "J3") (pin "33") (pinfunction "33_33") (pintype "bidirectional"))
    )
    (net (code "64") (name "XHDMI_HPD") (class "Default")
      (node (ref "IC3") (pin "4") (pinfunction "HPD_A-_4") (pintype "bidirectional"))
      (node (ref "J3") (pin "34") (pinfunction "34_34") (pintype "bidirectional"))
    )
    (net (code "65") (name "XHDMI_I2C_SCL") (class "Default")
      (node (ref "IC3") (pin "2") (pinfunction "SCL_A_2") (pintype "bidirectional"))
      (node (ref "J4") (pin "33") (pinfunction "33_33") (pintype "bidirectional"))
    )
    (net (code "66") (name "XHDMI_I2C_SDA") (class "Default")
      (node (ref "IC3") (pin "3") (pinfunction "SDA_A_3") (pintype "bidirectional"))
      (node (ref "J4") (pin "34") (pinfunction "34_34") (pintype "bidirectional"))
    )
    (net (code "67") (name "XHDMI_TX0_N") (class "Default")
      (node (ref "IC3") (pin "17") (pinfunction "D0-_17") (pintype "bidirectional"))
      (node (ref "J3") (pin "39") (pinfunction "39_39") (pintype "bidirectional"))
      (node (ref "J5") (pin "9") (pinfunction "D0-_9") (pintype "bidirectional"))
    )
    (net (code "68") (name "XHDMI_TX0_P") (class "Default")
      (node (ref "IC3") (pin "18") (pinfunction "D0+_18") (pintype "bidirectional"))
      (node (ref "J3") (pin "40") (pinfunction "40_40") (pintype "bidirectional"))
      (node (ref "J5") (pin "8") (pinfunction "D0+_8") (pintype "bidirectional"))
    )
    (net (code "69") (name "XHDMI_TX1_N") (class "Default")
      (node (ref "IC3") (pin "20") (pinfunction "D1-_20") (pintype "bidirectional"))
      (node (ref "J3") (pin "37") (pinfunction "37_37") (pintype "bidirectional"))
      (node (ref "J5") (pin "6") (pinfunction "D1-_6") (pintype "bidirectional"))
    )
    (net (code "70") (name "XHDMI_TX1_P") (class "Default")
      (node (ref "IC3") (pin "21") (pinfunction "D1+_21") (pintype "bidirectional"))
      (node (ref "J3") (pin "38") (pinfunction "38_38") (pintype "bidirectional"))
      (node (ref "J5") (pin "5") (pinfunction "D1+_5") (pintype "bidirectional"))
    )
    (net (code "71") (name "XHDMI_TX2_N") (class "Default")
      (node (ref "IC3") (pin "22") (pinfunction "D2-_22") (pintype "bidirectional"))
      (node (ref "J3") (pin "35") (pinfunction "35_35") (pintype "bidirectional"))
      (node (ref "J5") (pin "3") (pinfunction "D2-_3") (pintype "bidirectional"))
    )
    (net (code "72") (name "XHDMI_TX2_P") (class "Default")
      (node (ref "IC3") (pin "23") (pinfunction "D2+_23") (pintype "bidirectional"))
      (node (ref "J3") (pin "36") (pinfunction "36_36") (pintype "bidirectional"))
      (node (ref "J5") (pin "2") (pinfunction "D2+_2") (pintype "bidirectional"))
    )
    (net (code "73") (name "XHDMI_TXC_N") (class "Default")
      (node (ref "IC3") (pin "15") (pinfunction "CLK-_15") (pintype "input"))
      (node (ref "J3") (pin "41") (pinfunction "41_41") (pintype "bidirectional"))
      (node (ref "J5") (pin "12") (pinfunction "CLK-_12") (pintype "bidirectional"))
    )
    (net (code "74") (name "XHDMI_TXC_P") (class "Default")
      (node (ref "IC3") (pin "16") (pinfunction "CLK+_16") (pintype "input"))
      (node (ref "J3") (pin "42") (pinfunction "42_42") (pintype "bidirectional"))
      (node (ref "J5") (pin "11") (pinfunction "CLK+_11") (pintype "bidirectional"))
    )
    (net (code "75") (name "XI2C_SCL0") (class "Default")
      (node (ref "J4") (pin "31") (pinfunction "31_31") (pintype "bidirectional"))
      (node (ref "SV1") (pin "27") (pinfunction "27_27") (pintype "passive"))
    )
    (net (code "76") (name "XI2C_SCL1") (class "Default")
      (node (ref "J4") (pin "29") (pinfunction "29_29") (pintype "bidirectional"))
      (node (ref "SV1") (pin "25") (pinfunction "25_25") (pintype "passive"))
    )
    (net (code "77") (name "XI2C_SCL2") (class "Default")
      (node (ref "J4") (pin "27") (pinfunction "27_27") (pintype "bidirectional"))
      (node (ref "SV1") (pin "23") (pinfunction "23_23") (pintype "passive"))
    )
    (net (code "78") (name "XI2C_SDA0") (class "Default")
      (node (ref "J4") (pin "32") (pinfunction "32_32") (pintype "bidirectional"))
      (node (ref "SV1") (pin "28") (pinfunction "28_28") (pintype "passive"))
    )
    (net (code "79") (name "XI2C_SDA1") (class "Default")
      (node (ref "J4") (pin "30") (pinfunction "30_30") (pintype "bidirectional"))
      (node (ref "SV1") (pin "26") (pinfunction "26_26") (pintype "passive"))
    )
    (net (code "80") (name "XI2C_SDA2") (class "Default")
      (node (ref "J4") (pin "28") (pinfunction "28_28") (pintype "bidirectional"))
      (node (ref "SV1") (pin "24") (pinfunction "24_24") (pintype "passive"))
    )
    (net (code "81") (name "XI2S0_BCLK") (class "Default")
      (node (ref "J4") (pin "19") (pinfunction "19_19") (pintype "bidirectional"))
    )
    (net (code "82") (name "XI2S0_DIN") (class "Default")
      (node (ref "J4") (pin "18") (pinfunction "18_18") (pintype "bidirectional"))
    )
    (net (code "83") (name "XI2S0_DOUT") (class "Default")
      (node (ref "J4") (pin "17") (pinfunction "17_17") (pintype "bidirectional"))
    )
    (net (code "84") (name "XI2S0_LRCLK") (class "Default")
      (node (ref "J4") (pin "15") (pinfunction "15_15") (pintype "bidirectional"))
    )
    (net (code "85") (name "XI2S0_MCLK") (class "Default")
      (node (ref "J4") (pin "20") (pinfunction "20_20") (pintype "bidirectional"))
    )
    (net (code "86") (name "XMIPICSI_D0_N") (class "Default")
      (node (ref "J3") (pin "11") (pinfunction "11_11") (pintype "bidirectional"))
    )
    (net (code "87") (name "XMIPICSI_D0_P") (class "Default")
      (node (ref "J3") (pin "12") (pinfunction "12_12") (pintype "bidirectional"))
    )
    (net (code "88") (name "XMIPICSI_D1_N") (class "Default")
      (node (ref "J3") (pin "13") (pinfunction "13_13") (pintype "bidirectional"))
    )
    (net (code "89") (name "XMIPICSI_D1_P") (class "Default")
      (node (ref "J3") (pin "14") (pinfunction "14_14") (pintype "bidirectional"))
    )
    (net (code "90") (name "XMIPICSI_D2_N") (class "Default")
      (node (ref "J3") (pin "15") (pinfunction "15_15") (pintype "bidirectional"))
    )
    (net (code "91") (name "XMIPICSI_D2_P") (class "Default")
      (node (ref "J3") (pin "16") (pinfunction "16_16") (pintype "bidirectional"))
    )
    (net (code "92") (name "XMIPICSI_D3_N") (class "Default")
      (node (ref "J3") (pin "17") (pinfunction "17_17") (pintype "bidirectional"))
    )
    (net (code "93") (name "XMIPICSI_D3_P") (class "Default")
      (node (ref "J3") (pin "18") (pinfunction "18_18") (pintype "bidirectional"))
    )
    (net (code "94") (name "XMIPICSI_DCLK_N") (class "Default")
      (node (ref "J3") (pin "9") (pinfunction "9_9") (pintype "bidirectional"))
    )
    (net (code "95") (name "XMIPICSI_DCLK_P") (class "Default")
      (node (ref "J3") (pin "10") (pinfunction "10_10") (pintype "bidirectional"))
    )
    (net (code "96") (name "XMIPIDSI_D0_N") (class "Default")
      (node (ref "J3") (pin "23") (pinfunction "23_23") (pintype "bidirectional"))
    )
    (net (code "97") (name "XMIPIDSI_D0_P") (class "Default")
      (node (ref "J3") (pin "24") (pinfunction "24_24") (pintype "bidirectional"))
    )
    (net (code "98") (name "XMIPIDSI_D1_N") (class "Default")
      (node (ref "J3") (pin "25") (pinfunction "25_25") (pintype "bidirectional"))
    )
    (net (code "99") (name "XMIPIDSI_D1_P") (class "Default")
      (node (ref "J3") (pin "26") (pinfunction "26_26") (pintype "bidirectional"))
    )
    (net (code "100") (name "XMIPIDSI_D2_N") (class "Default")
      (node (ref "J3") (pin "27") (pinfunction "27_27") (pintype "bidirectional"))
    )
    (net (code "101") (name "XMIPIDSI_D2_P") (class "Default")
      (node (ref "J3") (pin "28") (pinfunction "28_28") (pintype "bidirectional"))
    )
    (net (code "102") (name "XMIPIDSI_D3_N") (class "Default")
      (node (ref "J3") (pin "29") (pinfunction "29_29") (pintype "bidirectional"))
    )
    (net (code "103") (name "XMIPIDSI_D3_P") (class "Default")
      (node (ref "J3") (pin "30") (pinfunction "30_30") (pintype "bidirectional"))
    )
    (net (code "104") (name "XMIPIDSI_DCLK_N") (class "Default")
      (node (ref "J3") (pin "21") (pinfunction "21_21") (pintype "bidirectional"))
    )
    (net (code "105") (name "XMIPIDSI_DCLK_P") (class "Default")
      (node (ref "J3") (pin "22") (pinfunction "22_22") (pintype "bidirectional"))
    )
    (net (code "106") (name "XNRESET") (class "Default")
      (node (ref "J4") (pin "11") (pinfunction "11_11") (pintype "bidirectional"))
      (node (ref "R10") (pin "2") (pinfunction "2_2") (pintype "passive"))
    )
    (net (code "107") (name "XOTG_D_N") (class "Default")
      (node (ref "J2") (pin "D-") (pinfunction "D-_D-") (pintype "bidirectional"))
      (node (ref "J3") (pin "45") (pinfunction "45_45") (pintype "bidirectional"))
    )
    (net (code "108") (name "XOTG_D_P") (class "Default")
      (node (ref "J2") (pin "D+") (pinfunction "D+_D+") (pintype "bidirectional"))
      (node (ref "J3") (pin "46") (pinfunction "46_46") (pintype "bidirectional"))
    )
    (net (code "109") (name "XOTG_ID") (class "Default")
      (node (ref "J2") (pin "ID") (pinfunction "ID_ID") (pintype "bidirectional"))
      (node (ref "J3") (pin "50") (pinfunction "50_50") (pintype "bidirectional"))
      (node (ref "R14") (pin "1") (pinfunction "1_1") (pintype "passive"))
    )
    (net (code "110") (name "XPGC27") (class "Default")
      (node (ref "J4") (pin "62") (pinfunction "62_62") (pintype "bidirectional"))
    )
    (net (code "111") (name "XPWERKEY") (class "Default")
      (node (ref "J4") (pin "9") (pinfunction "9_9") (pintype "bidirectional"))
      (node (ref "R9") (pin "2") (pinfunction "2_2") (pintype "passive"))
    )
    (net (code "112") (name "XPWM0") (class "Default")
      (node (ref "J4") (pin "26") (pinfunction "26_26") (pintype "bidirectional"))
      (node (ref "SV1") (pin "22") (pinfunction "22_22") (pintype "passive"))
    )
    (net (code "113") (name "XPWM1") (class "Default")
      (node (ref "J4") (pin "25") (pinfunction "25_25") (pintype "bidirectional"))
      (node (ref "SV1") (pin "21") (pinfunction "21_21") (pintype "passive"))
    )
    (net (code "114") (name "XSD0_CLK") (class "Default")
      (node (ref "J4") (pin "49") (pinfunction "49_49") (pintype "bidirectional"))
    )
    (net (code "115") (name "XSD0_CMD") (class "Default")
      (node (ref "J4") (pin "47") (pinfunction "47_47") (pintype "bidirectional"))
    )
    (net (code "116") (name "XSD0_D0") (class "Default")
      (node (ref "J4") (pin "52") (pinfunction "52_52") (pintype "bidirectional"))
    )
    (net (code "117") (name "XSD0_D1") (class "Default")
      (node (ref "J4") (pin "51") (pinfunction "51_51") (pintype "bidirectional"))
    )
    (net (code "118") (name "XSD0_D2") (class "Default")
      (node (ref "J4") (pin "50") (pinfunction "50_50") (pintype "bidirectional"))
    )
    (net (code "119") (name "XSD0_D3") (class "Default")
      (node (ref "J4") (pin "48") (pinfunction "48_48") (pintype "bidirectional"))
    )
    (net (code "120") (name "XSPI_CLK") (class "Default")
      (node (ref "J4") (pin "23") (pinfunction "23_23") (pintype "bidirectional"))
      (node (ref "SV1") (pin "19") (pinfunction "19_19") (pintype "passive"))
    )
    (net (code "121") (name "XSPI_CS") (class "Default")
      (node (ref "J4") (pin "24") (pinfunction "24_24") (pintype "bidirectional"))
      (node (ref "SV1") (pin "20") (pinfunction "20_20") (pintype "passive"))
    )
    (net (code "122") (name "XSPI_MISO") (class "Default")
      (node (ref "J4") (pin "21") (pinfunction "21_21") (pintype "bidirectional"))
      (node (ref "SV1") (pin "17") (pinfunction "17_17") (pintype "passive"))
    )
    (net (code "123") (name "XSPI_MOSI") (class "Default")
      (node (ref "J4") (pin "22") (pinfunction "22_22") (pintype "bidirectional"))
      (node (ref "SV1") (pin "18") (pinfunction "18_18") (pintype "passive"))
    )
    (net (code "124") (name "XUART_RX0") (class "Default")
      (node (ref "J4") (pin "46") (pinfunction "46_46") (pintype "bidirectional"))
      (node (ref "SV1") (pin "36") (pinfunction "36_36") (pintype "passive"))
    )
    (net (code "125") (name "XUART_RX1") (class "Default")
      (node (ref "J4") (pin "44") (pinfunction "44_44") (pintype "bidirectional"))
      (node (ref "SV1") (pin "34") (pinfunction "34_34") (pintype "passive"))
    )
    (net (code "126") (name "XUART_TX0") (class "Default")
      (node (ref "J4") (pin "45") (pinfunction "45_45") (pintype "bidirectional"))
      (node (ref "SV1") (pin "35") (pinfunction "35_35") (pintype "passive"))
    )
    (net (code "127") (name "XUART_TX1") (class "Default")
      (node (ref "J4") (pin "43") (pinfunction "43_43") (pintype "bidirectional"))
      (node (ref "SV1") (pin "33") (pinfunction "33_33") (pintype "passive"))
    )
    (net (code "128") (name "XUSBH_D_N") (class "Default")
      (node (ref "J3") (pin "47") (pinfunction "47_47") (pintype "bidirectional"))
    )
    (net (code "129") (name "XUSBH_D_P") (class "Default")
      (node (ref "J3") (pin "48") (pinfunction "48_48") (pintype "bidirectional"))
    )
    (net (code "130") (name "unconnected-(IC2-~{OC}-Pad3)") (class "Default")
      (node (ref "IC2") (pin "3") (pinfunction "~{OC}_3") (pintype "bidirectional"))
    )
    (net (code "131") (name "unconnected-(J3-Pad49)") (class "Default")
      (node (ref "J3") (pin "49") (pinfunction "49_49") (pintype "bidirectional"))
    )
    (net (code "132") (name "unconnected-(J3-Pad51)") (class "Default")
      (node (ref "J3") (pin "51") (pinfunction "51_51") (pintype "bidirectional"))
    )
    (net (code "133") (name "unconnected-(J3-Pad53)") (class "Default")
      (node (ref "J3") (pin "53") (pinfunction "53_53") (pintype "bidirectional"))
    )
    (net (code "134") (name "unconnected-(J3-Pad57)") (class "Default")
      (node (ref "J3") (pin "57") (pinfunction "57_57") (pintype "bidirectional"))
    )
    (net (code "135") (name "unconnected-(J3-Pad58)") (class "Default")
      (node (ref "J3") (pin "58") (pinfunction "58_58") (pintype "bidirectional"))
    )
    (net (code "136") (name "unconnected-(J3-Pad61)") (class "Default")
      (node (ref "J3") (pin "61") (pinfunction "61_61") (pintype "bidirectional"))
    )
    (net (code "137") (name "unconnected-(J3-Pad62)") (class "Default")
      (node (ref "J3") (pin "62") (pinfunction "62_62") (pintype "bidirectional"))
    )
    (net (code "138") (name "unconnected-(J4-Pad7)") (class "Default")
      (node (ref "J4") (pin "7") (pinfunction "7_7") (pintype "bidirectional"))
    )
    (net (code "139") (name "unconnected-(J4-Pad38)") (class "Default")
      (node (ref "J4") (pin "38") (pinfunction "38_38") (pintype "bidirectional"))
    )
    (net (code "140") (name "unconnected-(J4-Pad53)") (class "Default")
      (node (ref "J4") (pin "53") (pinfunction "53_53") (pintype "bidirectional"))
    )
    (net (code "141") (name "unconnected-(J4-Pad69)") (class "Default")
      (node (ref "J4") (pin "69") (pinfunction "69_69") (pintype "bidirectional"))
    )
    (net (code "142") (name "unconnected-(J5-UTILITY-Pad17)") (class "Default")
      (node (ref "J5") (pin "17") (pinfunction "UTILITY_17") (pintype "bidirectional"))
    )
    (net (code "143") (name "unconnected-(J6-1-PadDTR)") (class "Default")
      (node (ref "J6") (pin "DTR") (pinfunction "1_DTR") (pintype "passive"))
    )
    (net (code "144") (name "unconnected-(J6-4-PadVCC)") (class "Default")
      (node (ref "J6") (pin "VCC") (pinfunction "4_VCC") (pintype "passive"))
    )
    (net (code "145") (name "unconnected-(J6-5-PadCTS)") (class "Default")
      (node (ref "J6") (pin "CTS") (pinfunction "5_CTS") (pintype "passive"))
    )
    (net (code "146") (name "unconnected-(S3-Pad3)") (class "Default")
      (node (ref "S3") (pin "3") (pinfunction "3_3") (pintype "bidirectional"))
    )
    (net (code "147") (name "unconnected-(S3-Pad6)") (class "Default")
      (node (ref "S3") (pin "6") (pinfunction "6_6") (pintype "bidirectional"))
    )
  )
)
